# pm3_RF_dev_Rev_2.net
KiCad netlist of a schematic drawn in EAGLE
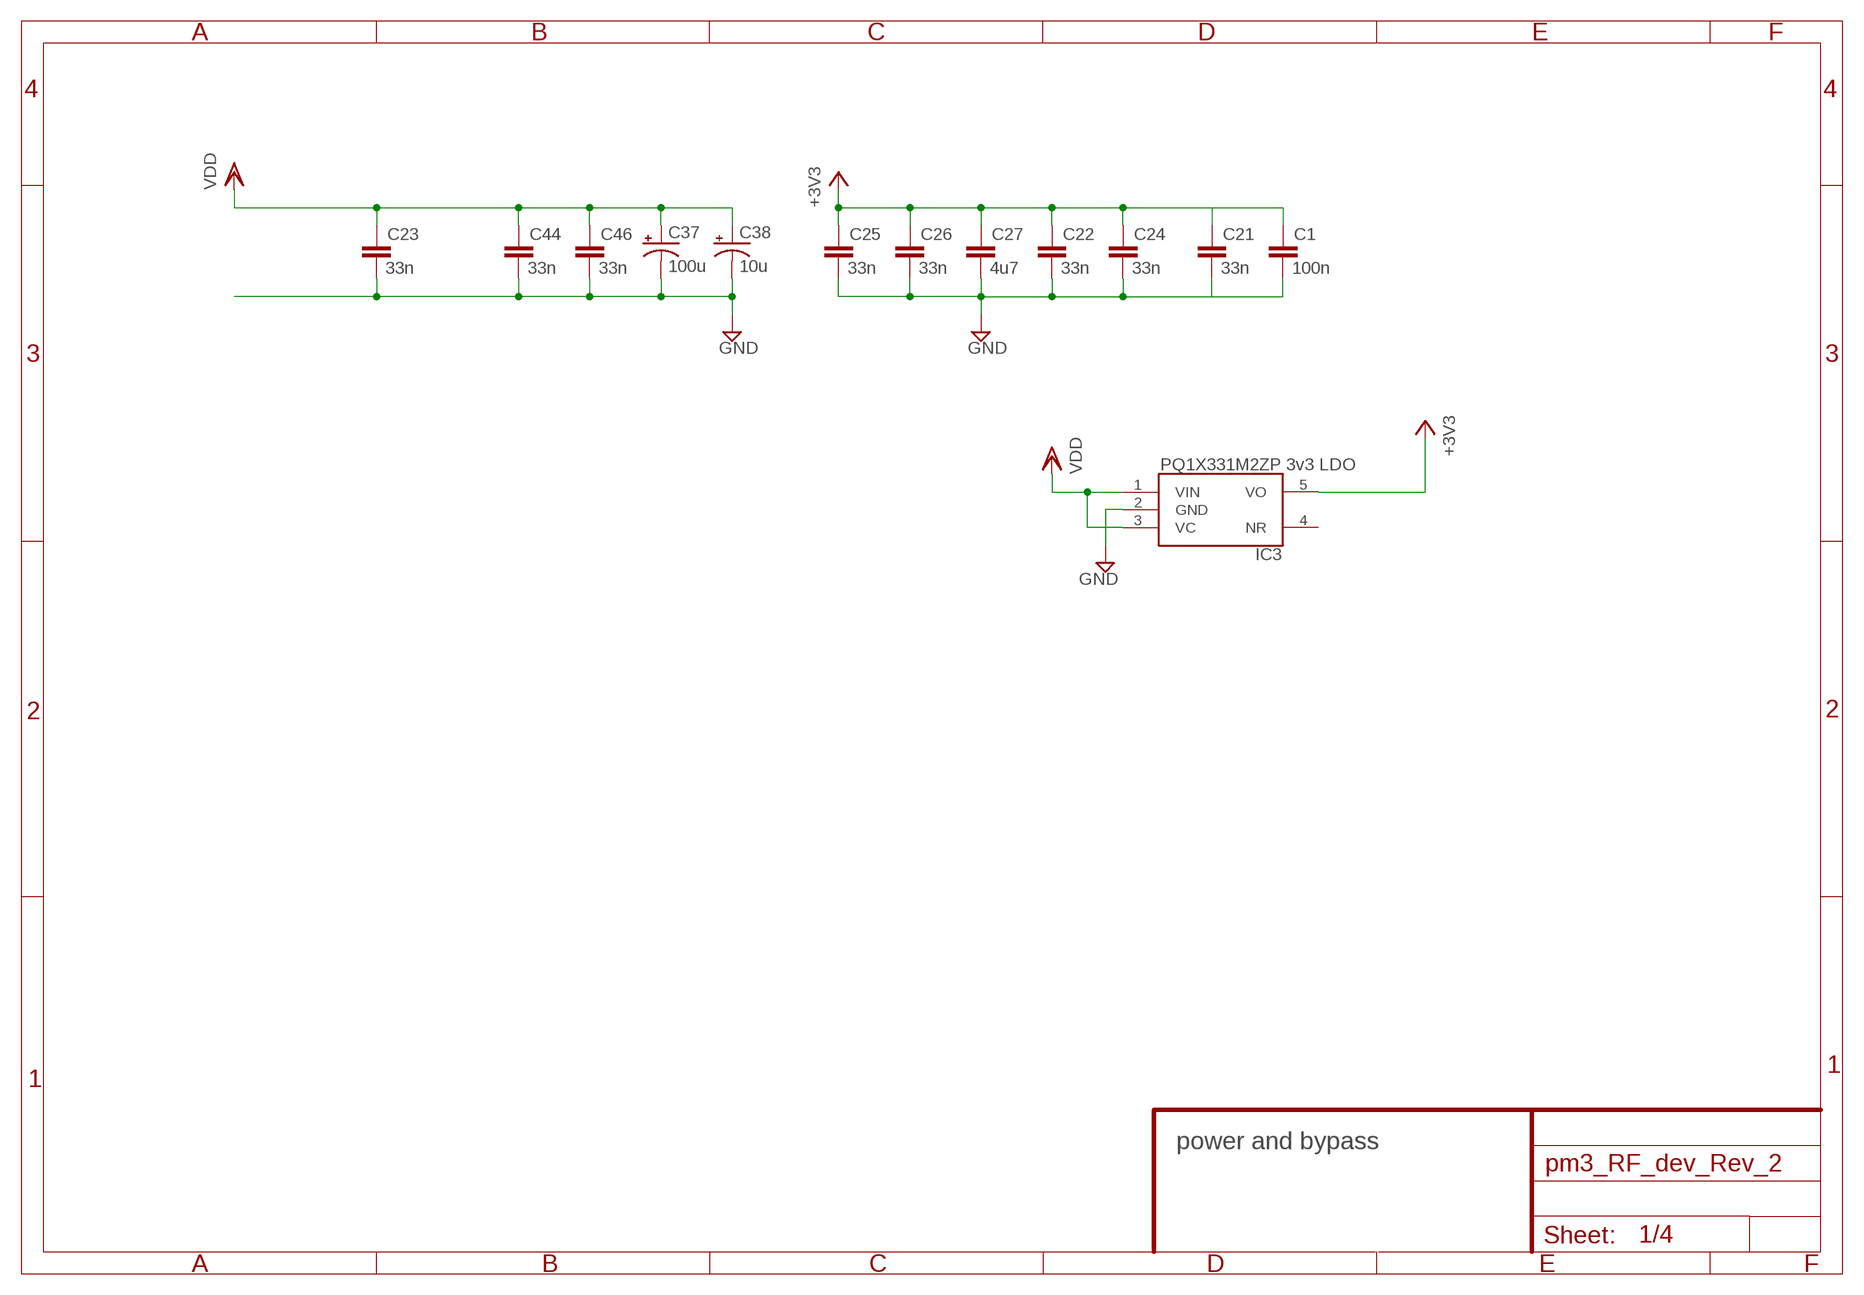
[diagram p0: schematic, sheet 1]
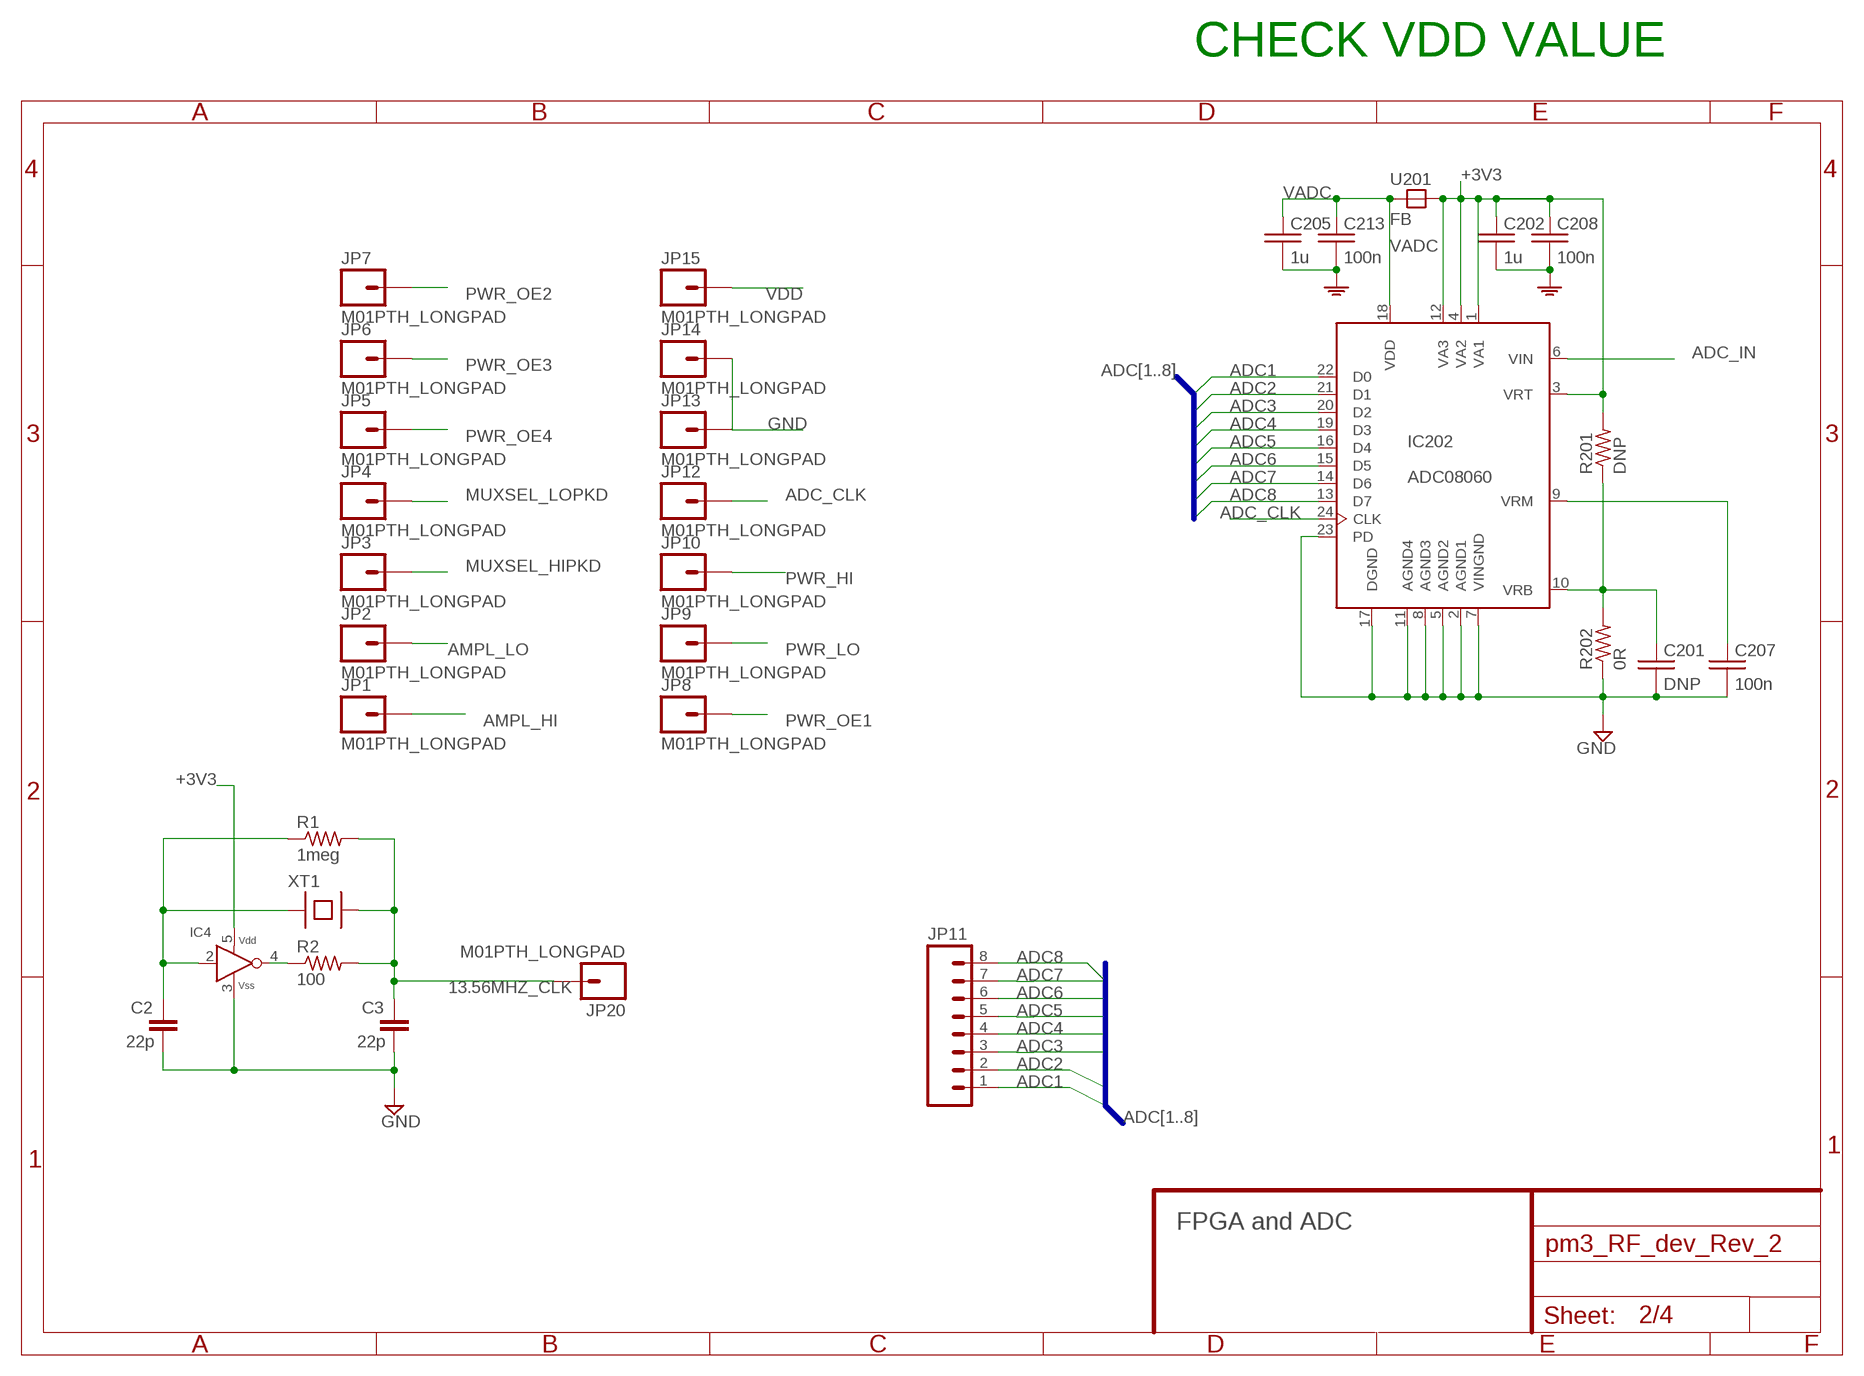
[diagram p1: schematic, sheet 2]
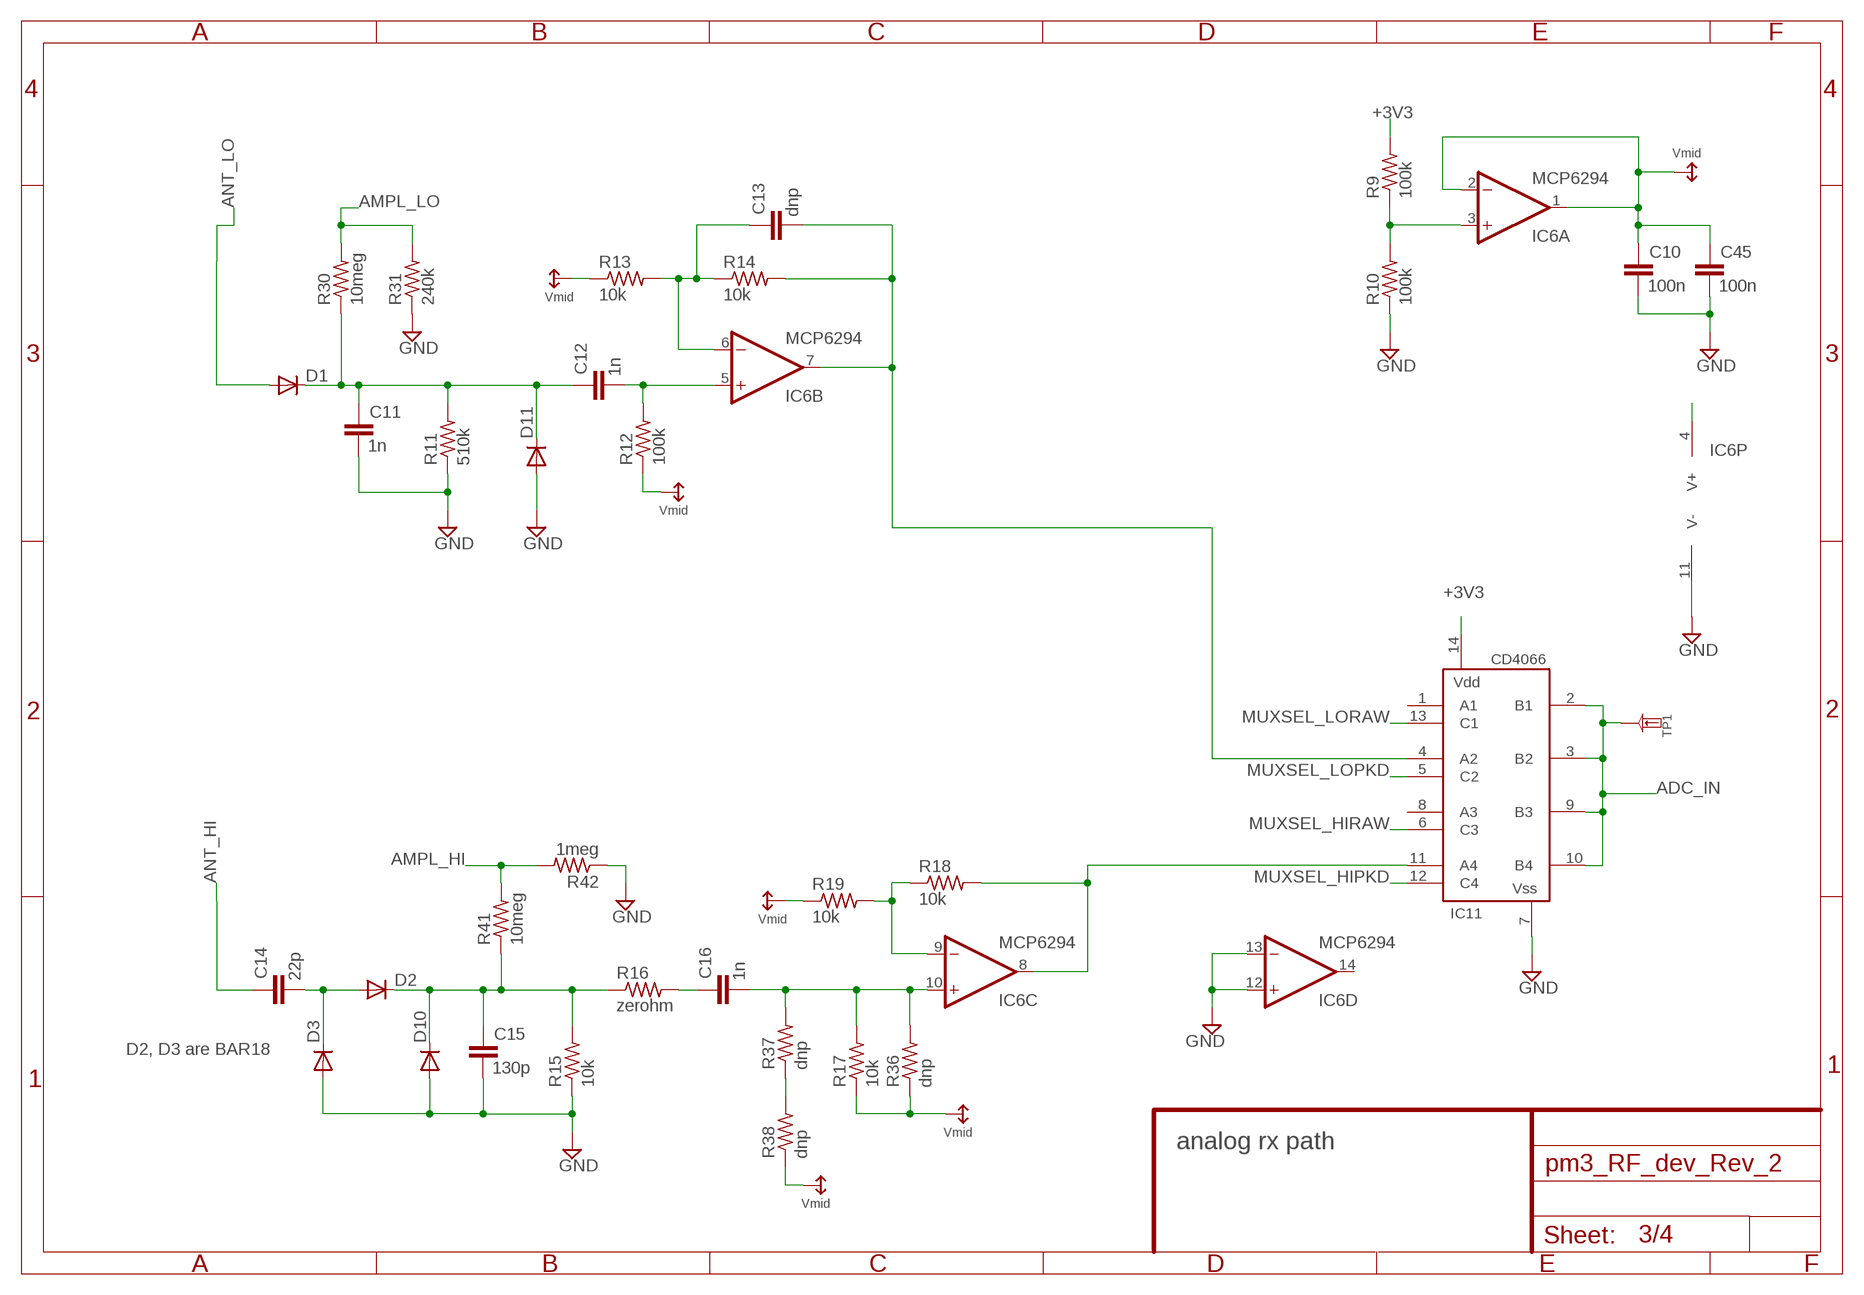
[diagram p2: schematic, sheet 3]
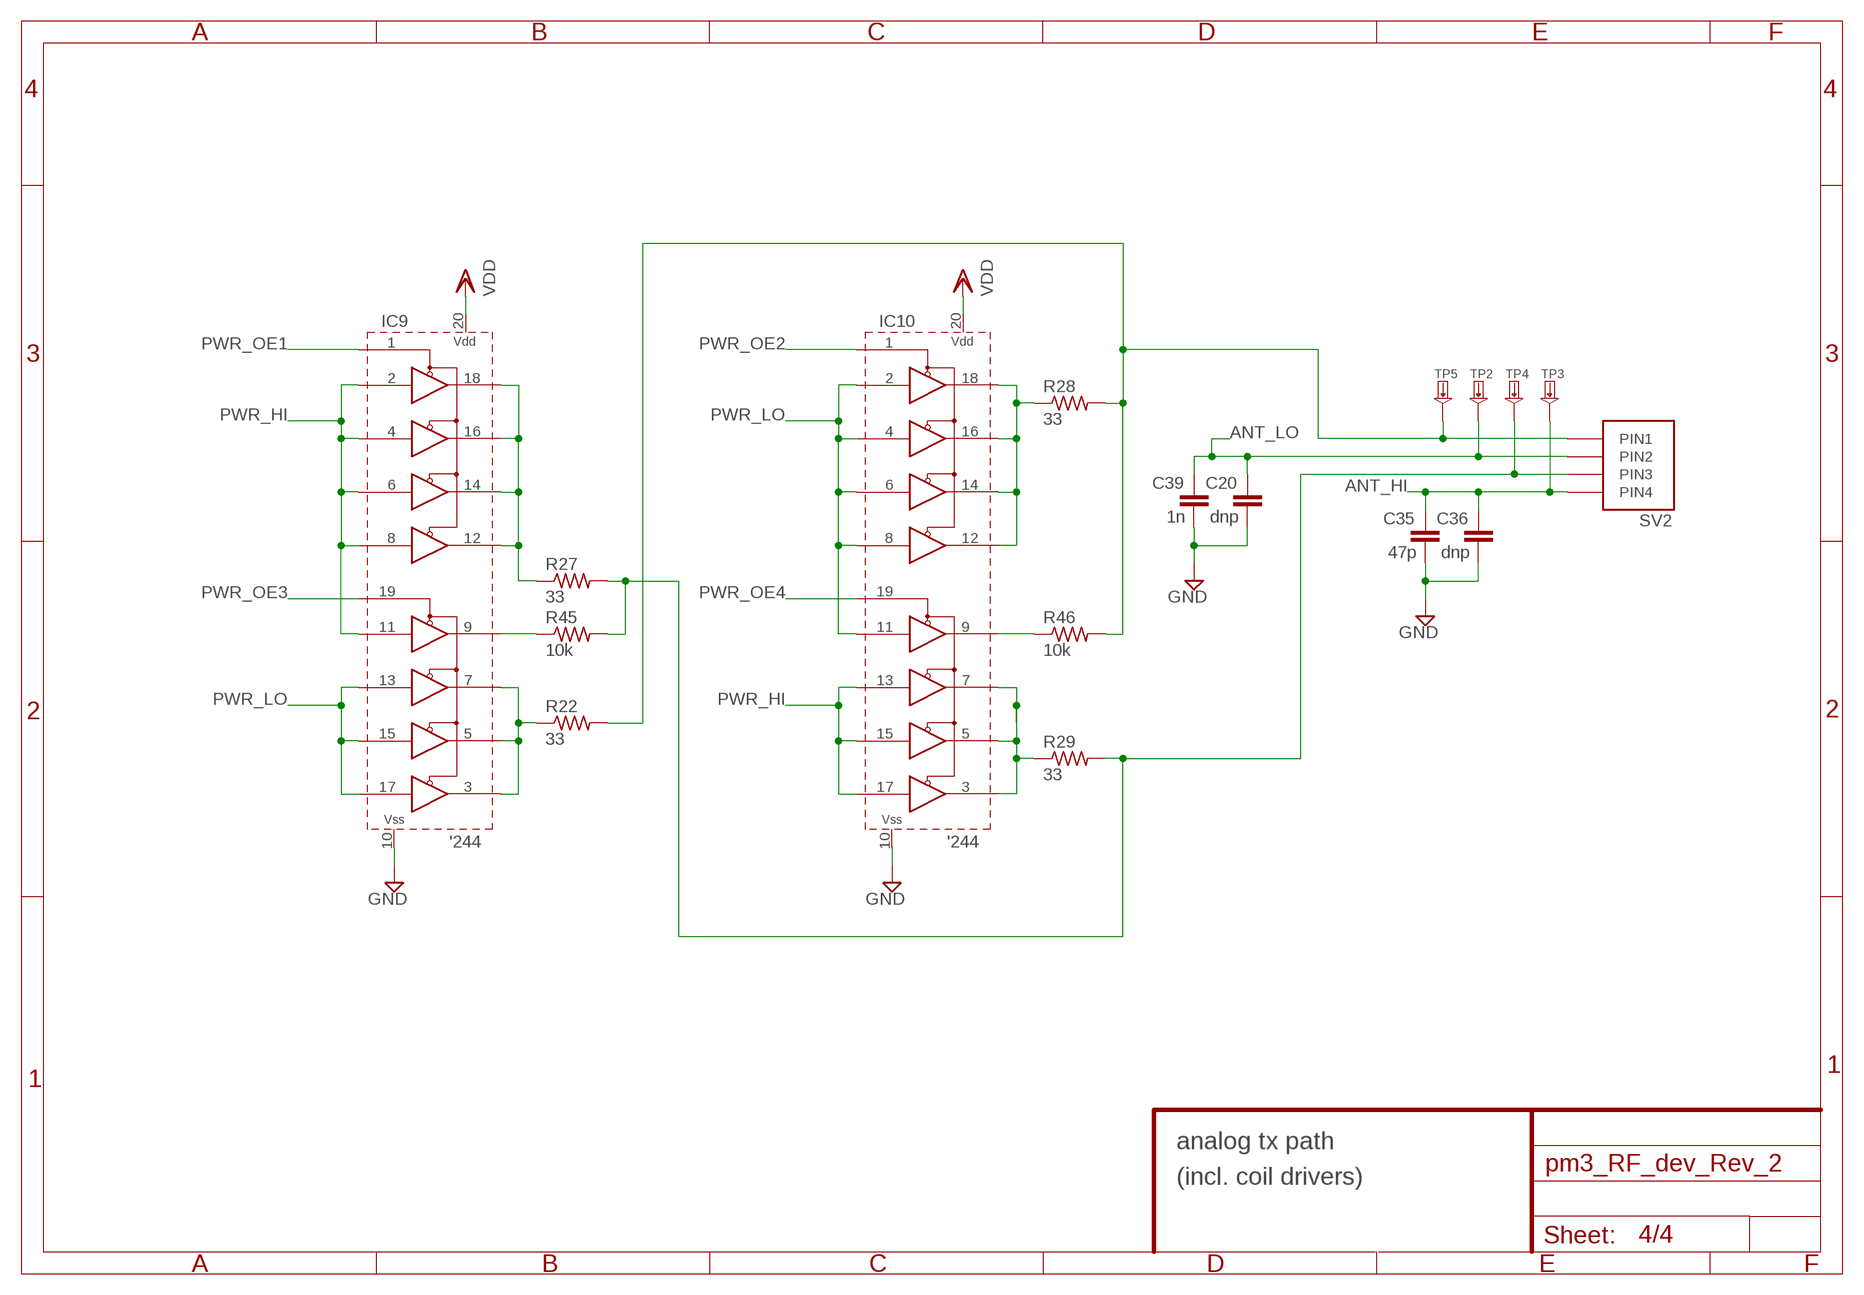
[diagram p3: schematic, sheet 4]

(export (version "E")
  (design (tool "Eeschema 10.0.6"))
  (components
    (comp (ref "C10")
      (value "100n")
      (footprint "eagle-import:RLC_0603")
      (libsource (lib "eagle-import") (part "CAPACITOR0603"))
    )
    (comp (ref "C11")
      (value "1n")
      (footprint "eagle-import:RLC_0603")
      (libsource (lib "eagle-import") (part "CAPACITOR0603"))
    )
    (comp (ref "C12")
      (value "1n")
      (footprint "eagle-import:RLC_0603")
      (libsource (lib "eagle-import") (part "CAPACITOR0603"))
    )
    (comp (ref "C13")
      (value "dnp")
      (footprint "eagle-import:RLC_0603")
      (libsource (lib "eagle-import") (part "CAPACITOR0603"))
    )
    (comp (ref "C14")
      (value "22p")
      (footprint "eagle-import:RLC_0603")
      (libsource (lib "eagle-import") (part "CAPACITOR0603"))
    )
    (comp (ref "C15")
      (value "130p")
      (footprint "eagle-import:RLC_0603")
      (libsource (lib "eagle-import") (part "CAPACITOR0603"))
    )
    (comp (ref "C16")
      (value "1n")
      (footprint "eagle-import:RLC_0603")
      (libsource (lib "eagle-import") (part "CAPACITOR0603"))
    )
    (comp (ref "C45")
      (value "100n")
      (footprint "eagle-import:RLC_0603")
      (libsource (lib "eagle-import") (part "CAPACITOR0603"))
    )
    (comp (ref "D1")
      (value "DIODE-SMD-SOT23")
      (footprint "eagle-import:SOT23-3LEAD")
      (libsource (lib "eagle-import") (part "DIODE-SMD-SOT23"))
    )
    (comp (ref "D2")
      (value "DIODE-SMD-SOT23")
      (footprint "eagle-import:SOT23-3LEAD")
      (libsource (lib "eagle-import") (part "DIODE-SMD-SOT23"))
    )
    (comp (ref "D3")
      (value "DIODE-SMD-SOT23")
      (footprint "eagle-import:SOT23-3LEAD")
      (libsource (lib "eagle-import") (part "DIODE-SMD-SOT23"))
    )
    (comp (ref "D10")
      (value "DIODE-SMD-SOT23")
      (footprint "eagle-import:SOT23-3LEAD")
      (libsource (lib "eagle-import") (part "DIODE-SMD-SOT23"))
    )
    (comp (ref "D11")
      (value "DIODE-SMD-SOT23")
      (footprint "eagle-import:SOT23-3LEAD")
      (libsource (lib "eagle-import") (part "DIODE-SMD-SOT23"))
    )
    (comp (ref "IC6")
      (value "MCP6294")
      (footprint "eagle-import:TSSOP-14")
      (libsource (lib "eagle-import") (part "OPAMP-TLC2274"))
    )
    (comp (ref "IC11")
      (value "CD4066")
      (footprint "eagle-import:TSSOP-14")
      (libsource (lib "eagle-import") (part "CD4066"))
    )
    (comp (ref "R9")
      (value "100k")
      (footprint "eagle-import:RLC_0603")
      (libsource (lib "eagle-import") (part "RESISTOR0603"))
    )
    (comp (ref "R10")
      (value "100k")
      (footprint "eagle-import:RLC_0603")
      (libsource (lib "eagle-import") (part "RESISTOR0603"))
    )
    (comp (ref "R11")
      (value "510k")
      (footprint "eagle-import:RLC_0603")
      (libsource (lib "eagle-import") (part "RESISTOR0603"))
    )
    (comp (ref "R12")
      (value "100k")
      (footprint "eagle-import:RLC_0603")
      (libsource (lib "eagle-import") (part "RESISTOR0603"))
    )
    (comp (ref "R13")
      (value "10k")
      (footprint "eagle-import:RLC_0603")
      (libsource (lib "eagle-import") (part "RESISTOR0603"))
    )
    (comp (ref "R14")
      (value "10k")
      (footprint "eagle-import:RLC_0603")
      (libsource (lib "eagle-import") (part "RESISTOR0603"))
    )
    (comp (ref "R15")
      (value "10k")
      (footprint "eagle-import:RLC_0603")
      (libsource (lib "eagle-import") (part "RESISTOR0603"))
    )
    (comp (ref "R16")
      (value "zerohm")
      (footprint "eagle-import:RLC_0603")
      (libsource (lib "eagle-import") (part "RESISTOR0603"))
    )
    (comp (ref "R17")
      (value "10k")
      (footprint "eagle-import:RLC_0603")
      (libsource (lib "eagle-import") (part "RESISTOR0603"))
    )
    (comp (ref "R18")
      (value "10k")
      (footprint "eagle-import:RLC_0603")
      (libsource (lib "eagle-import") (part "RESISTOR0603"))
    )
    (comp (ref "R19")
      (value "10k")
      (footprint "eagle-import:RLC_0603")
      (libsource (lib "eagle-import") (part "RESISTOR0603"))
    )
    (comp (ref "R30")
      (value "10meg")
      (footprint "eagle-import:RLC_0603")
      (libsource (lib "eagle-import") (part "RESISTOR0603"))
    )
    (comp (ref "R31")
      (value "240k")
      (footprint "eagle-import:RLC_0603")
      (libsource (lib "eagle-import") (part "RESISTOR0603"))
    )
    (comp (ref "R36")
      (value "dnp")
      (footprint "eagle-import:RLC_0603")
      (libsource (lib "eagle-import") (part "RESISTOR0603"))
    )
    (comp (ref "R37")
      (value "dnp")
      (footprint "eagle-import:RLC_0603")
      (libsource (lib "eagle-import") (part "RESISTOR0603"))
    )
    (comp (ref "R38")
      (value "dnp")
      (footprint "eagle-import:RLC_0603")
      (libsource (lib "eagle-import") (part "RESISTOR0603"))
    )
    (comp (ref "R41")
      (value "10meg")
      (footprint "eagle-import:RLC_0603")
      (libsource (lib "eagle-import") (part "RESISTOR0603"))
    )
    (comp (ref "R42")
      (value "1meg")
      (footprint "eagle-import:RLC_0603")
      (libsource (lib "eagle-import") (part "RESISTOR0603"))
    )
    (comp (ref "TP1")
      (value "TESTPADKEYSTONE-SMD")
      (footprint "eagle-import:KEYSTONE-SMD-TESTPOINT-5015")
      (libsource (lib "eagle-import") (part "TESTPADKEYSTONE-SMD"))
    )
    (comp (ref "C2")
      (value "22p")
      (footprint "eagle-import:RLC_0603")
      (libsource (lib "eagle-import") (part "CAPACITOR0603"))
    )
    (comp (ref "C3")
      (value "22p")
      (footprint "eagle-import:RLC_0603")
      (libsource (lib "eagle-import") (part "CAPACITOR0603"))
    )
    (comp (ref "C201")
      (value "DNP")
      (footprint "eagle-import:0603")
      (libsource (lib "eagle-import") (part "C-EU"))
    )
    (comp (ref "C202")
      (value "1u")
      (footprint "eagle-import:0603")
      (libsource (lib "eagle-import") (part "C-EU"))
    )
    (comp (ref "C205")
      (value "1u")
      (footprint "eagle-import:0603")
      (libsource (lib "eagle-import") (part "C-EU"))
    )
    (comp (ref "C207")
      (value "100n")
      (footprint "eagle-import:0603")
      (libsource (lib "eagle-import") (part "C-EU"))
    )
    (comp (ref "C208")
      (value "100n")
      (footprint "eagle-import:0603")
      (libsource (lib "eagle-import") (part "C-EU"))
    )
    (comp (ref "C213")
      (value "100n")
      (footprint "eagle-import:0603")
      (libsource (lib "eagle-import") (part "C-EU"))
    )
    (comp (ref "IC4")
      (value "HCU-INVERTER")
      (footprint "eagle-import:SMV-5")
      (libsource (lib "eagle-import") (part "HCU-INVERTER"))
    )
    (comp (ref "IC202")
      (value "ADC08060")
      (footprint "eagle-import:TSSOP24")
      (libsource (lib "eagle-import") (part "ADC08060"))
    )
    (comp (ref "JP1")
      (value "M01PTH_LONGPAD")
      (footprint "eagle-import:1X01_LONGPAD")
      (libsource (lib "eagle-import") (part "M01PTH_LONGPAD"))
    )
    (comp (ref "JP2")
      (value "M01PTH_LONGPAD")
      (footprint "eagle-import:1X01_LONGPAD")
      (libsource (lib "eagle-import") (part "M01PTH_LONGPAD"))
    )
    (comp (ref "JP3")
      (value "M01PTH_LONGPAD")
      (footprint "eagle-import:1X01_LONGPAD")
      (libsource (lib "eagle-import") (part "M01PTH_LONGPAD"))
    )
    (comp (ref "JP4")
      (value "M01PTH_LONGPAD")
      (footprint "eagle-import:1X01_LONGPAD")
      (libsource (lib "eagle-import") (part "M01PTH_LONGPAD"))
    )
    (comp (ref "JP5")
      (value "M01PTH_LONGPAD")
      (footprint "eagle-import:1X01_LONGPAD")
      (libsource (lib "eagle-import") (part "M01PTH_LONGPAD"))
    )
    (comp (ref "JP6")
      (value "M01PTH_LONGPAD")
      (footprint "eagle-import:1X01_LONGPAD")
      (libsource (lib "eagle-import") (part "M01PTH_LONGPAD"))
    )
    (comp (ref "JP7")
      (value "M01PTH_LONGPAD")
      (footprint "eagle-import:1X01_LONGPAD")
      (libsource (lib "eagle-import") (part "M01PTH_LONGPAD"))
    )
    (comp (ref "JP8")
      (value "M01PTH_LONGPAD")
      (footprint "eagle-import:1X01_LONGPAD")
      (libsource (lib "eagle-import") (part "M01PTH_LONGPAD"))
    )
    (comp (ref "JP9")
      (value "M01PTH_LONGPAD")
      (footprint "eagle-import:1X01_LONGPAD")
      (libsource (lib "eagle-import") (part "M01PTH_LONGPAD"))
    )
    (comp (ref "JP10")
      (value "M01PTH_LONGPAD")
      (footprint "eagle-import:1X01_LONGPAD")
      (libsource (lib "eagle-import") (part "M01PTH_LONGPAD"))
    )
    (comp (ref "JP11")
      (value "M08LONGPADS")
      (footprint "eagle-import:1X08_LONGPADS")
      (libsource (lib "eagle-import") (part "M08LONGPADS"))
    )
    (comp (ref "JP12")
      (value "M01PTH_LONGPAD")
      (footprint "eagle-import:1X01_LONGPAD")
      (libsource (lib "eagle-import") (part "M01PTH_LONGPAD"))
    )
    (comp (ref "JP13")
      (value "M01PTH_LONGPAD")
      (footprint "eagle-import:1X01_LONGPAD")
      (libsource (lib "eagle-import") (part "M01PTH_LONGPAD"))
    )
    (comp (ref "JP14")
      (value "M01PTH_LONGPAD")
      (footprint "eagle-import:1X01_LONGPAD")
      (libsource (lib "eagle-import") (part "M01PTH_LONGPAD"))
    )
    (comp (ref "JP15")
      (value "M01PTH_LONGPAD")
      (footprint "eagle-import:1X01_LONGPAD")
      (libsource (lib "eagle-import") (part "M01PTH_LONGPAD"))
    )
    (comp (ref "JP20")
      (value "M01PTH_LONGPAD")
      (footprint "eagle-import:1X01_LONGPAD")
      (libsource (lib "eagle-import") (part "M01PTH_LONGPAD"))
    )
    (comp (ref "R1")
      (value "1meg")
      (footprint "eagle-import:RLC_0603")
      (libsource (lib "eagle-import") (part "RESISTOR0603"))
    )
    (comp (ref "R2")
      (value "100")
      (footprint "eagle-import:RLC_0603")
      (libsource (lib "eagle-import") (part "RESISTOR0603"))
    )
    (comp (ref "R201")
      (value "DNP")
      (footprint "eagle-import:0603")
      (libsource (lib "eagle-import") (part "R-US"))
    )
    (comp (ref "R202")
      (value "0R")
      (footprint "eagle-import:0603")
      (libsource (lib "eagle-import") (part "R-US"))
    )
    (comp (ref "U201")
      (value "FB")
      (footprint "eagle-import:0805")
      (libsource (lib "eagle-import") (part "FB"))
    )
    (comp (ref "XT1")
      (value "XTAL-SMD-CITIZEN-CS10")
      (footprint "eagle-import:XTAL-SMD-CITIZEN-CS10")
      (libsource (lib "eagle-import") (part "XTAL-SMD-CITIZEN-CS10"))
    )
    (comp (ref "C20")
      (value "dnp")
      (footprint "eagle-import:RLC_0603")
      (libsource (lib "eagle-import") (part "CAPACITOR0603"))
    )
    (comp (ref "C35")
      (value "47p")
      (footprint "eagle-import:RLC_0603")
      (libsource (lib "eagle-import") (part "CAPACITOR0603"))
    )
    (comp (ref "C36")
      (value "dnp")
      (footprint "eagle-import:RLC_0603")
      (libsource (lib "eagle-import") (part "CAPACITOR0603"))
    )
    (comp (ref "C39")
      (value "1n")
      (footprint "eagle-import:RLC_0603")
      (libsource (lib "eagle-import") (part "CAPACITOR0603"))
    )
    (comp (ref "IC9")
      (value "74XX244-OCTAL-TRISTATE-BUFFERS")
      (footprint "eagle-import:TSSOP-20")
      (libsource (lib "eagle-import") (part "74XX244-OCTAL-TRISTATE-BUFFERS"))
    )
    (comp (ref "IC10")
      (value "74XX244-OCTAL-TRISTATE-BUFFERS")
      (footprint "eagle-import:TSSOP-20")
      (libsource (lib "eagle-import") (part "74XX244-OCTAL-TRISTATE-BUFFERS"))
    )
    (comp (ref "R22")
      (value "33")
      (footprint "eagle-import:RLC_0603")
      (libsource (lib "eagle-import") (part "RESISTOR0603"))
    )
    (comp (ref "R27")
      (value "33")
      (footprint "eagle-import:RLC_0603")
      (libsource (lib "eagle-import") (part "RESISTOR0603"))
    )
    (comp (ref "R28")
      (value "33")
      (footprint "eagle-import:RLC_0603")
      (libsource (lib "eagle-import") (part "RESISTOR0603"))
    )
    (comp (ref "R29")
      (value "33")
      (footprint "eagle-import:RLC_0603")
      (libsource (lib "eagle-import") (part "RESISTOR0603"))
    )
    (comp (ref "R45")
      (value "10k")
      (footprint "eagle-import:RLC_0603")
      (libsource (lib "eagle-import") (part "RESISTOR0603"))
    )
    (comp (ref "R46")
      (value "10k")
      (footprint "eagle-import:RLC_0603")
      (libsource (lib "eagle-import") (part "RESISTOR0603"))
    )
    (comp (ref "SV2")
      (value "HIROSE-MQ172-4POS")
      (footprint "eagle-import:HIROSE-MQ172-4POS")
      (libsource (lib "eagle-import") (part "HIROSE-MQ172-4POS"))
    )
    (comp (ref "TP2")
      (value "TESTPADKEYSTONE-SMD")
      (footprint "eagle-import:KEYSTONE-SMD-TESTPOINT-5015")
      (libsource (lib "eagle-import") (part "TESTPADKEYSTONE-SMD"))
    )
    (comp (ref "TP3")
      (value "TESTPADKEYSTONE-SMD")
      (footprint "eagle-import:KEYSTONE-SMD-TESTPOINT-5015")
      (libsource (lib "eagle-import") (part "TESTPADKEYSTONE-SMD"))
    )
    (comp (ref "TP4")
      (value "TESTPADKEYSTONE-SMD")
      (footprint "eagle-import:KEYSTONE-SMD-TESTPOINT-5015")
      (libsource (lib "eagle-import") (part "TESTPADKEYSTONE-SMD"))
    )
    (comp (ref "TP5")
      (value "TESTPADKEYSTONE-SMD")
      (footprint "eagle-import:KEYSTONE-SMD-TESTPOINT-5015")
      (libsource (lib "eagle-import") (part "TESTPADKEYSTONE-SMD"))
    )
    (comp (ref "C1")
      (value "100n")
      (footprint "eagle-import:RLC_0603")
      (libsource (lib "eagle-import") (part "CAPACITOR0603"))
    )
    (comp (ref "C21")
      (value "33n")
      (footprint "eagle-import:RLC_0603")
      (libsource (lib "eagle-import") (part "CAPACITOR0603"))
    )
    (comp (ref "C22")
      (value "33n")
      (footprint "eagle-import:RLC_0603")
      (libsource (lib "eagle-import") (part "CAPACITOR0603"))
    )
    (comp (ref "C23")
      (value "33n")
      (footprint "eagle-import:RLC_0603")
      (libsource (lib "eagle-import") (part "CAPACITOR0603"))
    )
    (comp (ref "C24")
      (value "33n")
      (footprint "eagle-import:RLC_0603")
      (libsource (lib "eagle-import") (part "CAPACITOR0603"))
    )
    (comp (ref "C25")
      (value "33n")
      (footprint "eagle-import:RLC_0603")
      (libsource (lib "eagle-import") (part "CAPACITOR0603"))
    )
    (comp (ref "C26")
      (value "33n")
      (footprint "eagle-import:RLC_0603")
      (libsource (lib "eagle-import") (part "CAPACITOR0603"))
    )
    (comp (ref "C27")
      (value "4u7")
      (footprint "eagle-import:RLC_1210")
      (libsource (lib "eagle-import") (part "CAPACITOR1210"))
    )
    (comp (ref "C37")
      (value "100u")
      (footprint "eagle-import:CAPCAITOR-ELECTROLYTIC-ALCHIP-MZA-F80")
      (libsource (lib "eagle-import") (part "CAPACITOR-POLARIZEDALCHIP-MZA-F80"))
    )
    (comp (ref "C38")
      (value "10u")
      (footprint "eagle-import:CAPCAITOR-ELECTROLYTIC-ALCHIP-MZA-F80")
      (libsource (lib "eagle-import") (part "CAPACITOR-POLARIZEDALCHIP-MZA-F80"))
    )
    (comp (ref "C44")
      (value "33n")
      (footprint "eagle-import:RLC_0603")
      (libsource (lib "eagle-import") (part "CAPACITOR0603"))
    )
    (comp (ref "C46")
      (value "33n")
      (footprint "eagle-import:RLC_0603")
      (libsource (lib "eagle-import") (part "CAPACITOR0603"))
    )
    (comp (ref "IC3")
      (value "PQ1X331M2ZP-3V3-LDO-SOT-23-5")
      (footprint "eagle-import:SOT-23-5")
      (libsource (lib "eagle-import") (part "PQ1X331M2ZP-3V3-LDO-SOT-23-5"))
    )
  )
  (nets
    (net (code "1") (name "+3V3") (class "Default")
      (node (ref "C1") (pin "1") (pinfunction "1_1") (pintype "passive"))
      (node (ref "C202") (pin "1") (pinfunction "1_1") (pintype "passive"))
      (node (ref "C208") (pin "1") (pinfunction "1_1") (pintype "passive"))
      (node (ref "C21") (pin "1") (pinfunction "1_1") (pintype "passive"))
      (node (ref "C22") (pin "1") (pinfunction "1_1") (pintype "passive"))
      (node (ref "C24") (pin "1") (pinfunction "1_1") (pintype "passive"))
      (node (ref "C25") (pin "1") (pinfunction "1_1") (pintype "passive"))
      (node (ref "C26") (pin "1") (pinfunction "1_1") (pintype "passive"))
      (node (ref "C27") (pin "1") (pinfunction "1_1") (pintype "passive"))
      (node (ref "IC11") (pin "14") (pinfunction "VDD_14") (pintype "bidirectional"))
      (node (ref "IC202") (pin "1") (pinfunction "VA1_1") (pintype "passive"))
      (node (ref "IC202") (pin "12") (pinfunction "VA3_12") (pintype "passive"))
      (node (ref "IC202") (pin "3") (pinfunction "VRT_3") (pintype "input"))
      (node (ref "IC202") (pin "4") (pinfunction "VA2_4") (pintype "passive"))
      (node (ref "IC3") (pin "5") (pinfunction "VO_5") (pintype "bidirectional"))
      (node (ref "IC4") (pin "5") (pinfunction "VDD_5") (pintype "bidirectional"))
      (node (ref "IC6") (pin "4") (pinfunction "V+_4") (pintype "bidirectional"))
      (node (ref "R201") (pin "2") (pinfunction "2_2") (pintype "passive"))
      (node (ref "R9") (pin "2") (pinfunction "2_2") (pintype "passive"))
      (node (ref "U201") (pin "2") (pinfunction "B_2") (pintype "passive"))
    )
    (net (code "3") (name "13.56MHZ_CLK") (class "Default")
      (node (ref "C3") (pin "1") (pinfunction "1_1") (pintype "passive"))
      (node (ref "JP20") (pin "1") (pinfunction "1_1") (pintype "passive"))
      (node (ref "R1") (pin "2") (pinfunction "2_2") (pintype "passive"))
      (node (ref "R2") (pin "2") (pinfunction "2_2") (pintype "passive"))
      (node (ref "XT1") (pin "B") (pinfunction "B_B") (pintype "bidirectional"))
    )
    (net (code "4") (name "ADC1") (class "Default")
      (node (ref "IC202") (pin "22") (pinfunction "D0_22") (pintype "output"))
      (node (ref "JP11") (pin "1") (pinfunction "1_1") (pintype "passive"))
    )
    (net (code "5") (name "ADC2") (class "Default")
      (node (ref "IC202") (pin "21") (pinfunction "D1_21") (pintype "output"))
      (node (ref "JP11") (pin "2") (pinfunction "2_2") (pintype "passive"))
    )
    (net (code "6") (name "ADC3") (class "Default")
      (node (ref "IC202") (pin "20") (pinfunction "D2_20") (pintype "output"))
      (node (ref "JP11") (pin "3") (pinfunction "3_3") (pintype "passive"))
    )
    (net (code "7") (name "ADC4") (class "Default")
      (node (ref "IC202") (pin "19") (pinfunction "D3_19") (pintype "output"))
      (node (ref "JP11") (pin "4") (pinfunction "4_4") (pintype "passive"))
    )
    (net (code "8") (name "ADC5") (class "Default")
      (node (ref "IC202") (pin "16") (pinfunction "D4_16") (pintype "output"))
      (node (ref "JP11") (pin "5") (pinfunction "5_5") (pintype "passive"))
    )
    (net (code "9") (name "ADC6") (class "Default")
      (node (ref "IC202") (pin "15") (pinfunction "D5_15") (pintype "output"))
      (node (ref "JP11") (pin "6") (pinfunction "6_6") (pintype "passive"))
    )
    (net (code "10") (name "ADC7") (class "Default")
      (node (ref "IC202") (pin "14") (pinfunction "D6_14") (pintype "output"))
      (node (ref "JP11") (pin "7") (pinfunction "7_7") (pintype "passive"))
    )
    (net (code "11") (name "ADC8") (class "Default")
      (node (ref "IC202") (pin "13") (pinfunction "D7_13") (pintype "output"))
      (node (ref "JP11") (pin "8") (pinfunction "8_8") (pintype "passive"))
    )
    (net (code "12") (name "ADC_CLK") (class "Default")
      (node (ref "IC202") (pin "24") (pinfunction "CLK_24") (pintype "input"))
      (node (ref "JP12") (pin "1") (pinfunction "1_1") (pintype "passive"))
    )
    (net (code "13") (name "ADC_IN") (class "Default")
      (node (ref "IC11") (pin "10") (pinfunction "B4_10") (pintype "passive"))
      (node (ref "IC11") (pin "2") (pinfunction "B1_2") (pintype "passive"))
      (node (ref "IC11") (pin "3") (pinfunction "B2_3") (pintype "passive"))
      (node (ref "IC11") (pin "9") (pinfunction "B3_9") (pintype "passive"))
      (node (ref "IC202") (pin "6") (pinfunction "VIN_6") (pintype "input"))
      (node (ref "TP1") (pin "1") (pinfunction "P$1_1") (pintype "bidirectional"))
    )
    (net (code "14") (name "AMPL_HI") (class "Default")
      (node (ref "JP1") (pin "1") (pinfunction "1_1") (pintype "passive"))
      (node (ref "R41") (pin "2") (pinfunction "2_2") (pintype "passive"))
      (node (ref "R42") (pin "2") (pinfunction "2_2") (pintype "passive"))
    )
    (net (code "15") (name "AMPL_LO") (class "Default")
      (node (ref "JP2") (pin "1") (pinfunction "1_1") (pintype "passive"))
      (node (ref "R30") (pin "2") (pinfunction "2_2") (pintype "passive"))
      (node (ref "R31") (pin "2") (pinfunction "2_2") (pintype "passive"))
    )
    (net (code "16") (name "ANT_HI") (class "Default")
      (node (ref "C14") (pin "1") (pinfunction "1_1") (pintype "passive"))
      (node (ref "C35") (pin "1") (pinfunction "1_1") (pintype "passive"))
      (node (ref "C36") (pin "1") (pinfunction "1_1") (pintype "passive"))
      (node (ref "SV2") (pin "4") (pinfunction "PIN4_4") (pintype "passive"))
      (node (ref "TP3") (pin "1") (pinfunction "P$1_1") (pintype "bidirectional"))
    )
    (net (code "17") (name "ANT_LO") (class "Default")
      (node (ref "C20") (pin "1") (pinfunction "1_1") (pintype "passive"))
      (node (ref "C39") (pin "1") (pinfunction "1_1") (pintype "passive"))
      (node (ref "D1") (pin "1") (pinfunction "A_1") (pintype "passive"))
      (node (ref "SV2") (pin "2") (pinfunction "PIN2_2") (pintype "passive"))
      (node (ref "TP2") (pin "1") (pinfunction "P$1_1") (pintype "bidirectional"))
    )
    (net (code "18") (name "GND") (class "Default")
      (node (ref "C1") (pin "2") (pinfunction "2_2") (pintype "passive"))
      (node (ref "C10") (pin "2") (pinfunction "2_2") (pintype "passive"))
      (node (ref "C11") (pin "2") (pinfunction "2_2") (pintype "passive"))
      (node (ref "C15") (pin "2") (pinfunction "2_2") (pintype "passive"))
      (node (ref "C2") (pin "2") (pinfunction "2_2") (pintype "passive"))
      (node (ref "C20") (pin "2") (pinfunction "2_2") (pintype "passive"))
      (node (ref "C201") (pin "2") (pinfunction "2_2") (pintype "passive"))
      (node (ref "C202") (pin "2") (pinfunction "2_2") (pintype "passive"))
      (node (ref "C205") (pin "2") (pinfunction "2_2") (pintype "passive"))
      (node (ref "C207") (pin "2") (pinfunction "2_2") (pintype "passive"))
      (node (ref "C208") (pin "2") (pinfunction "2_2") (pintype "passive"))
      (node (ref "C21") (pin "2") (pinfunction "2_2") (pintype "passive"))
      (node (ref "C213") (pin "2") (pinfunction "2_2") (pintype "passive"))
      (node (ref "C22") (pin "2") (pinfunction "2_2") (pintype "passive"))
      (node (ref "C23") (pin "2") (pinfunction "2_2") (pintype "passive"))
      (node (ref "C24") (pin "2") (pinfunction "2_2") (pintype "passive"))
      (node (ref "C25") (pin "2") (pinfunction "2_2") (pintype "passive"))
      (node (ref "C26") (pin "2") (pinfunction "2_2") (pintype "passive"))
      (node (ref "C27") (pin "2") (pinfunction "2_2") (pintype "passive"))
      (node (ref "C3") (pin "2") (pinfunction "2_2") (pintype "passive"))
      (node (ref "C35") (pin "2") (pinfunction "2_2") (pintype "passive"))
      (node (ref "C36") (pin "2") (pinfunction "2_2") (pintype "passive"))
      (node (ref "C37") (pin "-") (pinfunction "-_-") (pintype "passive"))
      (node (ref "C38") (pin "-") (pinfunction "-_-") (pintype "passive"))
      (node (ref "C39") (pin "2") (pinfunction "2_2") (pintype "passive"))
      (node (ref "C44") (pin "2") (pinfunction "2_2") (pintype "passive"))
      (node (ref "C45") (pin "2") (pinfunction "2_2") (pintype "passive"))
      (node (ref "C46") (pin "2") (pinfunction "2_2") (pintype "passive"))
      (node (ref "D10") (pin "1") (pinfunction "A_1") (pintype "passive"))
      (node (ref "D11") (pin "1") (pinfunction "A_1") (pintype "passive"))
      (node (ref "D3") (pin "1") (pinfunction "A_1") (pintype "passive"))
      (node (ref "IC10") (pin "10") (pinfunction "VSS_10") (pintype "bidirectional"))
      (node (ref "IC11") (pin "7") (pinfunction "VSS_7") (pintype "bidirectional"))
      (node (ref "IC202") (pin "11") (pinfunction "AGND4_11") (pintype "passive"))
      (node (ref "IC202") (pin "17") (pinfunction "DGND_17") (pintype "passive"))
      (node (ref "IC202") (pin "2") (pinfunction "AGND1_2") (pintype "passive"))
      (node (ref "IC202") (pin "23") (pinfunction "PD_23") (pintype "input"))
      (node (ref "IC202") (pin "5") (pinfunction "AGND2_5") (pintype "passive"))
      (node (ref "IC202") (pin "7") (pinfunction "VINGND_7") (pintype "input"))
      (node (ref "IC202") (pin "8") (pinfunction "AGND3_8") (pintype "passive"))
      (node (ref "IC3") (pin "2") (pinfunction "GND_2") (pintype "bidirectional"))
      (node (ref "IC4") (pin "3") (pinfunction "VSS_3") (pintype "bidirectional"))
      (node (ref "IC6") (pin "11") (pinfunction "V-_11") (pintype "bidirectional"))
      (node (ref "IC6") (pin "12") (pinfunction "+IN_12") (pintype "input"))
      (node (ref "IC6") (pin "13") (pinfunction "-IN_13") (pintype "input"))
      (node (ref "IC9") (pin "10") (pinfunction "VSS_10") (pintype "bidirectional"))
      (node (ref "JP13") (pin "1") (pinfunction "1_1") (pintype "passive"))
      (node (ref "JP14") (pin "1") (pinfunction "1_1") (pintype "passive"))
      (node (ref "R10") (pin "1") (pinfunction "1_1") (pintype "passive"))
      (node (ref "R11") (pin "1") (pinfunction "1_1") (pintype "passive"))
      (node (ref "R15") (pin "1") (pinfunction "1_1") (pintype "passive"))
      (node (ref "R202") (pin "1") (pinfunction "1_1") (pintype "passive"))
      (node (ref "R31") (pin "1") (pinfunction "1_1") (pintype "passive"))
      (node (ref "R42") (pin "1") (pinfunction "1_1") (pintype "passive"))
    )
    (net (code "19") (name "MUXSEL_HIPKD") (class "Default")
      (node (ref "IC11") (pin "12") (pinfunction "C4_12") (pintype "input"))
      (node (ref "JP3") (pin "1") (pinfunction "1_1") (pintype "passive"))
    )
    (net (code "20") (name "MUXSEL_HIRAW") (class "Default")
      (node (ref "IC11") (pin "6") (pinfunction "C3_6") (pintype "input"))
    )
    (net (code "21") (name "MUXSEL_LOPKD") (class "Default")
      (node (ref "IC11") (pin "5") (pinfunction "C2_5") (pintype "input"))
      (node (ref "JP4") (pin "1") (pinfunction "1_1") (pintype "passive"))
    )
    (net (code "22") (name "MUXSEL_LORAW") (class "Default")
      (node (ref "IC11") (pin "13") (pinfunction "C1_13") (pintype "input"))
    )
    (net (code "23") (name "Net-(C16-Pad1)") (class "Default")
      (node (ref "C16") (pin "1") (pinfunction "1_1") (pintype "passive"))
      (node (ref "R16") (pin "2") (pinfunction "2_2") (pintype "passive"))
    )
    (net (code "24") (name "Net-(D1-C)") (class "Default")
      (node (ref "C11") (pin "1") (pinfunction "1_1") (pintype "passive"))
      (node (ref "C12") (pin "1") (pinfunction "1_1") (pintype "passive"))
      (node (ref "D1") (pin "3") (pinfunction "C_3") (pintype "passive"))
      (node (ref "D11") (pin "3") (pinfunction "C_3") (pintype "passive"))
      (node (ref "R11") (pin "2") (pinfunction "2_2") (pintype "passive"))
      (node (ref "R30") (pin "1") (pinfunction "1_1") (pintype "passive"))
    )
    (net (code "25") (name "Net-(D2-A)") (class "Default")
      (node (ref "C14") (pin "2") (pinfunction "2_2") (pintype "passive"))
      (node (ref "D2") (pin "1") (pinfunction "A_1") (pintype "passive"))
      (node (ref "D3") (pin "3") (pinfunction "C_3") (pintype "passive"))
    )
    (net (code "26") (name "Net-(D10-C)") (class "Default")
      (node (ref "C15") (pin "1") (pinfunction "1_1") (pintype "passive"))
      (node (ref "D10") (pin "3") (pinfunction "C_3") (pintype "passive"))
      (node (ref "D2") (pin "3") (pinfunction "C_3") (pintype "passive"))
      (node (ref "R15") (pin "2") (pinfunction "2_2") (pintype "passive"))
      (node (ref "R16") (pin "1") (pinfunction "1_1") (pintype "passive"))
      (node (ref "R41") (pin "1") (pinfunction "1_1") (pintype "passive"))
    )
    (net (code "27") (name "Net-(IC4-A)") (class "Default")
      (node (ref "C2") (pin "1") (pinfunction "1_1") (pintype "passive"))
      (node (ref "IC4") (pin "2") (pinfunction "A_2") (pintype "bidirectional"))
      (node (ref "R1") (pin "1") (pinfunction "1_1") (pintype "passive"))
      (node (ref "XT1") (pin "A") (pinfunction "A_A") (pintype "bidirectional"))
    )
    (net (code "28") (name "Net-(IC4-Y)") (class "Default")
      (node (ref "IC4") (pin "4") (pinfunction "Y_4") (pintype "bidirectional"))
      (node (ref "R2") (pin "1") (pinfunction "1_1") (pintype "passive"))
    )
    (net (code "29") (name "Net-(IC6A-+IN)") (class "Default")
      (node (ref "IC6") (pin "3") (pinfunction "+IN_3") (pintype "input"))
      (node (ref "R10") (pin "2") (pinfunction "2_2") (pintype "passive"))
      (node (ref "R9") (pin "1") (pinfunction "1_1") (pintype "passive"))
    )
    (net (code "30") (name "Net-(IC6B-+IN)") (class "Default")
      (node (ref "C12") (pin "2") (pinfunction "2_2") (pintype "passive"))
      (node (ref "IC6") (pin "5") (pinfunction "+IN_5") (pintype "input"))
      (node (ref "R12") (pin "2") (pinfunction "2_2") (pintype "passive"))
    )
    (net (code "31") (name "Net-(IC6B--IN)") (class "Default")
      (node (ref "C13") (pin "1") (pinfunction "1_1") (pintype "passive"))
      (node (ref "IC6") (pin "6") (pinfunction "-IN_6") (pintype "input"))
      (node (ref "R13") (pin "2") (pinfunction "2_2") (pintype "passive"))
      (node (ref "R14") (pin "1") (pinfunction "1_1") (pintype "passive"))
    )
    (net (code "32") (name "Net-(IC6C-+IN)") (class "Default")
      (node (ref "C16") (pin "2") (pinfunction "2_2") (pintype "passive"))
      (node (ref "IC6") (pin "10") (pinfunction "+IN_10") (pintype "input"))
      (node (ref "R17") (pin "2") (pinfunction "2_2") (pintype "passive"))
      (node (ref "R36") (pin "2") (pinfunction "2_2") (pintype "passive"))
      (node (ref "R37") (pin "2") (pinfunction "2_2") (pintype "passive"))
    )
    (net (code "33") (name "Net-(IC6C--IN)") (class "Default")
      (node (ref "IC6") (pin "9") (pinfunction "-IN_9") (pintype "input"))
      (node (ref "R18") (pin "1") (pinfunction "1_1") (pintype "passive"))
      (node (ref "R19") (pin "2") (pinfunction "2_2") (pintype "passive"))
    )
    (net (code "34") (name "Net-(IC9-1Y1)") (class "Default")
      (node (ref "IC9") (pin "12") (pinfunction "1Y4_12") (pintype "bidirectional"))
      (node (ref "IC9") (pin "14") (pinfunction "1Y3_14") (pintype "bidirectional"))
      (node (ref "IC9") (pin "16") (pinfunction "1Y2_16") (pintype "bidirectional"))
      (node (ref "IC9") (pin "18") (pinfunction "1Y1_18") (pintype "bidirectional"))
      (node (ref "R27") (pin "1") (pinfunction "1_1") (pintype "passive"))
    )
    (net (code "35") (name "Net-(IC9-2Y1)") (class "Default")
      (node (ref "IC9") (pin "9") (pinfunction "2Y1_9") (pintype "bidirectional"))
      (node (ref "R45") (pin "1") (pinfunction "1_1") (pintype "passive"))
    )
    (net (code "36") (name "Net-(IC9-2Y2)") (class "Default")
      (node (ref "IC9") (pin "3") (pinfunction "2Y4_3") (pintype "bidirectional"))
      (node (ref "IC9") (pin "5") (pinfunction "2Y3_5") (pintype "bidirectional"))
      (node (ref "IC9") (pin "7") (pinfunction "2Y2_7") (pintype "bidirectional"))
      (node (ref "R22") (pin "1") (pinfunction "1_1") (pintype "passive"))
    )
    (net (code "37") (name "Net-(IC10-1Y1)") (class "Default")
      (node (ref "IC10") (pin "12") (pinfunction "1Y4_12") (pintype "bidirectional"))
      (node (ref "IC10") (pin "14") (pinfunction "1Y3_14") (pintype "bidirectional"))
      (node (ref "IC10") (pin "16") (pinfunction "1Y2_16") (pintype "bidirectional"))
      (node (ref "IC10") (pin "18") (pinfunction "1Y1_18") (pintype "bidirectional"))
      (node (ref "R28") (pin "1") (pinfunction "1_1") (pintype "passive"))
    )
    (net (code "38") (name "Net-(IC10-2Y1)") (class "Default")
      (node (ref "IC10") (pin "9") (pinfunction "2Y1_9") (pintype "bidirectional"))
      (node (ref "R46") (pin "1") (pinfunction "1_1") (pintype "passive"))
    )
    (net (code "39") (name "Net-(IC10-2Y2)") (class "Default")
      (node (ref "IC10") (pin "3") (pinfunction "2Y4_3") (pintype "bidirectional"))
      (node (ref "IC10") (pin "5") (pinfunction "2Y3_5") (pintype "bidirectional"))
      (node (ref "IC10") (pin "7") (pinfunction "2Y2_7") (pintype "bidirectional"))
      (node (ref "R29") (pin "1") (pinfunction "1_1") (pintype "passive"))
    )
    (net (code "40") (name "Net-(IC11-A2)") (class "Default")
      (node (ref "C13") (pin "2") (pinfunction "2_2") (pintype "passive"))
      (node (ref "IC11") (pin "4") (pinfunction "A2_4") (pintype "passive"))
      (node (ref "IC6") (pin "7") (pinfunction "OUT_7") (pintype "output"))
      (node (ref "R14") (pin "2") (pinfunction "2_2") (pintype "passive"))
    )
    (net (code "41") (name "Net-(IC11-A4)") (class "Default")
      (node (ref "IC11") (pin "11") (pinfunction "A4_11") (pintype "passive"))
      (node (ref "IC6") (pin "8") (pinfunction "OUT_8") (pintype "output"))
      (node (ref "R18") (pin "2") (pinfunction "2_2") (pintype "passive"))
    )
    (net (code "42") (name "Net-(IC202-VRB)") (class "Default")
      (node (ref "C201") (pin "1") (pinfunction "1_1") (pintype "passive"))
      (node (ref "IC202") (pin "10") (pinfunction "VRB_10") (pintype "input"))
      (node (ref "R201") (pin "1") (pinfunction "1_1") (pintype "passive"))
      (node (ref "R202") (pin "2") (pinfunction "2_2") (pintype "passive"))
    )
    (net (code "43") (name "Net-(IC202-VRM)") (class "Default")
      (node (ref "C207") (pin "1") (pinfunction "1_1") (pintype "passive"))
      (node (ref "IC202") (pin "9") (pinfunction "VRM_9") (pintype "input"))
    )
    (net (code "44") (name "Net-(R37-Pad1)") (class "Default")
      (node (ref "R37") (pin "1") (pinfunction "1_1") (pintype "passive"))
      (node (ref "R38") (pin "2") (pinfunction "2_2") (pintype "passive"))
    )
    (net (code "45") (name "Net-(SV2-PIN1)") (class "Default")
      (node (ref "R22") (pin "2") (pinfunction "2_2") (pintype "passive"))
      (node (ref "R28") (pin "2") (pinfunction "2_2") (pintype "passive"))
      (node (ref "R46") (pin "2") (pinfunction "2_2") (pintype "passive"))
      (node (ref "SV2") (pin "1") (pinfunction "PIN1_1") (pintype "passive"))
      (node (ref "TP5") (pin "1") (pinfunction "P$1_1") (pintype "bidirectional"))
    )
    (net (code "46") (name "Net-(SV2-PIN3)") (class "Default")
      (node (ref "R27") (pin "2") (pinfunction "2_2") (pintype "passive"))
      (node (ref "R29") (pin "2") (pinfunction "2_2") (pintype "passive"))
      (node (ref "R45") (pin "2") (pinfunction "2_2") (pintype "passive"))
      (node (ref "SV2") (pin "3") (pinfunction "PIN3_3") (pintype "passive"))
      (node (ref "TP4") (pin "1") (pinfunction "P$1_1") (pintype "bidirectional"))
    )
    (net (code "47") (name "PWR_HI") (class "Default")
      (node (ref "IC10") (pin "13") (pinfunction "2A2_13") (pintype "bidirectional"))
      (node (ref "IC10") (pin "15") (pinfunction "2A3_15") (pintype "bidirectional"))
      (node (ref "IC10") (pin "17") (pinfunction "2A4_17") (pintype "bidirectional"))
      (node (ref "IC9") (pin "11") (pinfunction "2A1_11") (pintype "bidirectional"))
      (node (ref "IC9") (pin "2") (pinfunction "1A1_2") (pintype "bidirectional"))
      (node (ref "IC9") (pin "4") (pinfunction "1A2_4") (pintype "bidirectional"))
      (node (ref "IC9") (pin "6") (pinfunction "1A3_6") (pintype "bidirectional"))
      (node (ref "IC9") (pin "8") (pinfunction "1A4_8") (pintype "bidirectional"))
      (node (ref "JP10") (pin "1") (pinfunction "1_1") (pintype "passive"))
    )
    (net (code "48") (name "PWR_LO") (class "Default")
      (node (ref "IC10") (pin "11") (pinfunction "2A1_11") (pintype "bidirectional"))
      (node (ref "IC10") (pin "2") (pinfunction "1A1_2") (pintype "bidirectional"))
      (node (ref "IC10") (pin "4") (pinfunction "1A2_4") (pintype "bidirectional"))
      (node (ref "IC10") (pin "6") (pinfunction "1A3_6") (pintype "bidirectional"))
      (node (ref "IC10") (pin "8") (pinfunction "1A4_8") (pintype "bidirectional"))
      (node (ref "IC9") (pin "13") (pinfunction "2A2_13") (pintype "bidirectional"))
      (node (ref "IC9") (pin "15") (pinfunction "2A3_15") (pintype "bidirectional"))
      (node (ref "IC9") (pin "17") (pinfunction "2A4_17") (pintype "bidirectional"))
      (node (ref "JP9") (pin "1") (pinfunction "1_1") (pintype "passive"))
    )
    (net (code "49") (name "PWR_OE1") (class "Default")
      (node (ref "IC9") (pin "1") (pinfunction "1NOE_1") (pintype "bidirectional"))
      (node (ref "JP8") (pin "1") (pinfunction "1_1") (pintype "passive"))
    )
    (net (code "50") (name "PWR_OE2") (class "Default")
      (node (ref "IC10") (pin "1") (pinfunction "1NOE_1") (pintype "bidirectional"))
      (node (ref "JP7") (pin "1") (pinfunction "1_1") (pintype "passive"))
    )
    (net (code "51") (name "PWR_OE3") (class "Default")
      (node (ref "IC9") (pin "19") (pinfunction "2NOE_19") (pintype "bidirectional"))
      (node (ref "JP6") (pin "1") (pinfunction "1_1") (pintype "passive"))
    )
    (net (code "52") (name "PWR_OE4") (class "Default")
      (node (ref "IC10") (pin "19") (pinfunction "2NOE_19") (pintype "bidirectional"))
      (node (ref "JP5") (pin "1") (pinfunction "1_1") (pintype "passive"))
    )
    (net (code "53") (name "VADC") (class "Default")
      (node (ref "C205") (pin "1") (pinfunction "1_1") (pintype "passive"))
      (node (ref "C213") (pin "1") (pinfunction "1_1") (pintype "passive"))
      (node (ref "IC202") (pin "18") (pinfunction "VDD_18") (pintype "passive"))
      (node (ref "U201") (pin "1") (pinfunction "A_1") (pintype "passive"))
    )
    (net (code "54") (name "VDD") (class "Default")
      (node (ref "C23") (pin "1") (pinfunction "1_1") (pintype "passive"))
      (node (ref "C37") (pin "+") (pinfunction "+_+") (pintype "passive"))
      (node (ref "C38") (pin "+") (pinfunction "+_+") (pintype "passive"))
      (node (ref "C44") (pin "1") (pinfunction "1_1") (pintype "passive"))
      (node (ref "C46") (pin "1") (pinfunction "1_1") (pintype "passive"))
      (node (ref "IC10") (pin "20") (pinfunction "VDD_20") (pintype "bidirectional"))
      (node (ref "IC3") (pin "1") (pinfunction "VIN_1") (pintype "bidirectional"))
      (node (ref "IC3") (pin "3") (pinfunction "VC_3") (pintype "bidirectional"))
      (node (ref "IC9") (pin "20") (pinfunction "VDD_20") (pintype "bidirectional"))
      (node (ref "JP15") (pin "1") (pinfunction "1_1") (pintype "passive"))
    )
    (net (code "55") (name "VMID") (class "Default")
      (node (ref "C10") (pin "1") (pinfunction "1_1") (pintype "passive"))
      (node (ref "C45") (pin "1") (pinfunction "1_1") (pintype "passive"))
      (node (ref "IC6") (pin "1") (pinfunction "OUT_1") (pintype "output"))
      (node (ref "IC6") (pin "2") (pinfunction "-IN_2") (pintype "input"))
      (node (ref "R12") (pin "1") (pinfunction "1_1") (pintype "passive"))
      (node (ref "R13") (pin "1") (pinfunction "1_1") (pintype "passive"))
      (node (ref "R17") (pin "1") (pinfunction "1_1") (pintype "passive"))
      (node (ref "R19") (pin "1") (pinfunction "1_1") (pintype "passive"))
      (node (ref "R36") (pin "1") (pinfunction "1_1") (pintype "passive"))
      (node (ref "R38") (pin "1") (pinfunction "1_1") (pintype "passive"))
    )
    (net (code "56") (name "unconnected-(IC3-NR-Pad4)") (class "Default")
      (node (ref "IC3") (pin "4") (pinfunction "NR_4") (pintype "bidirectional"))
    )
    (net (code "57") (name "unconnected-(IC6D-OUT-Pad14)") (class "Default")
      (node (ref "IC6") (pin "14") (pinfunction "OUT_14") (pintype "output"))
    )
    (net (code "58") (name "unconnected-(IC11-A1-Pad1)") (class "Default")
      (node (ref "IC11") (pin "1") (pinfunction "A1_1") (pintype "passive"))
    )
    (net (code "59") (name "unconnected-(IC11-A3-Pad8)") (class "Default")
      (node (ref "IC11") (pin "8") (pinfunction "A3_8") (pintype "passive"))
    )
  )
)
